# IHM.net
KiCad netlist of a schematic drawn in Altium Designer
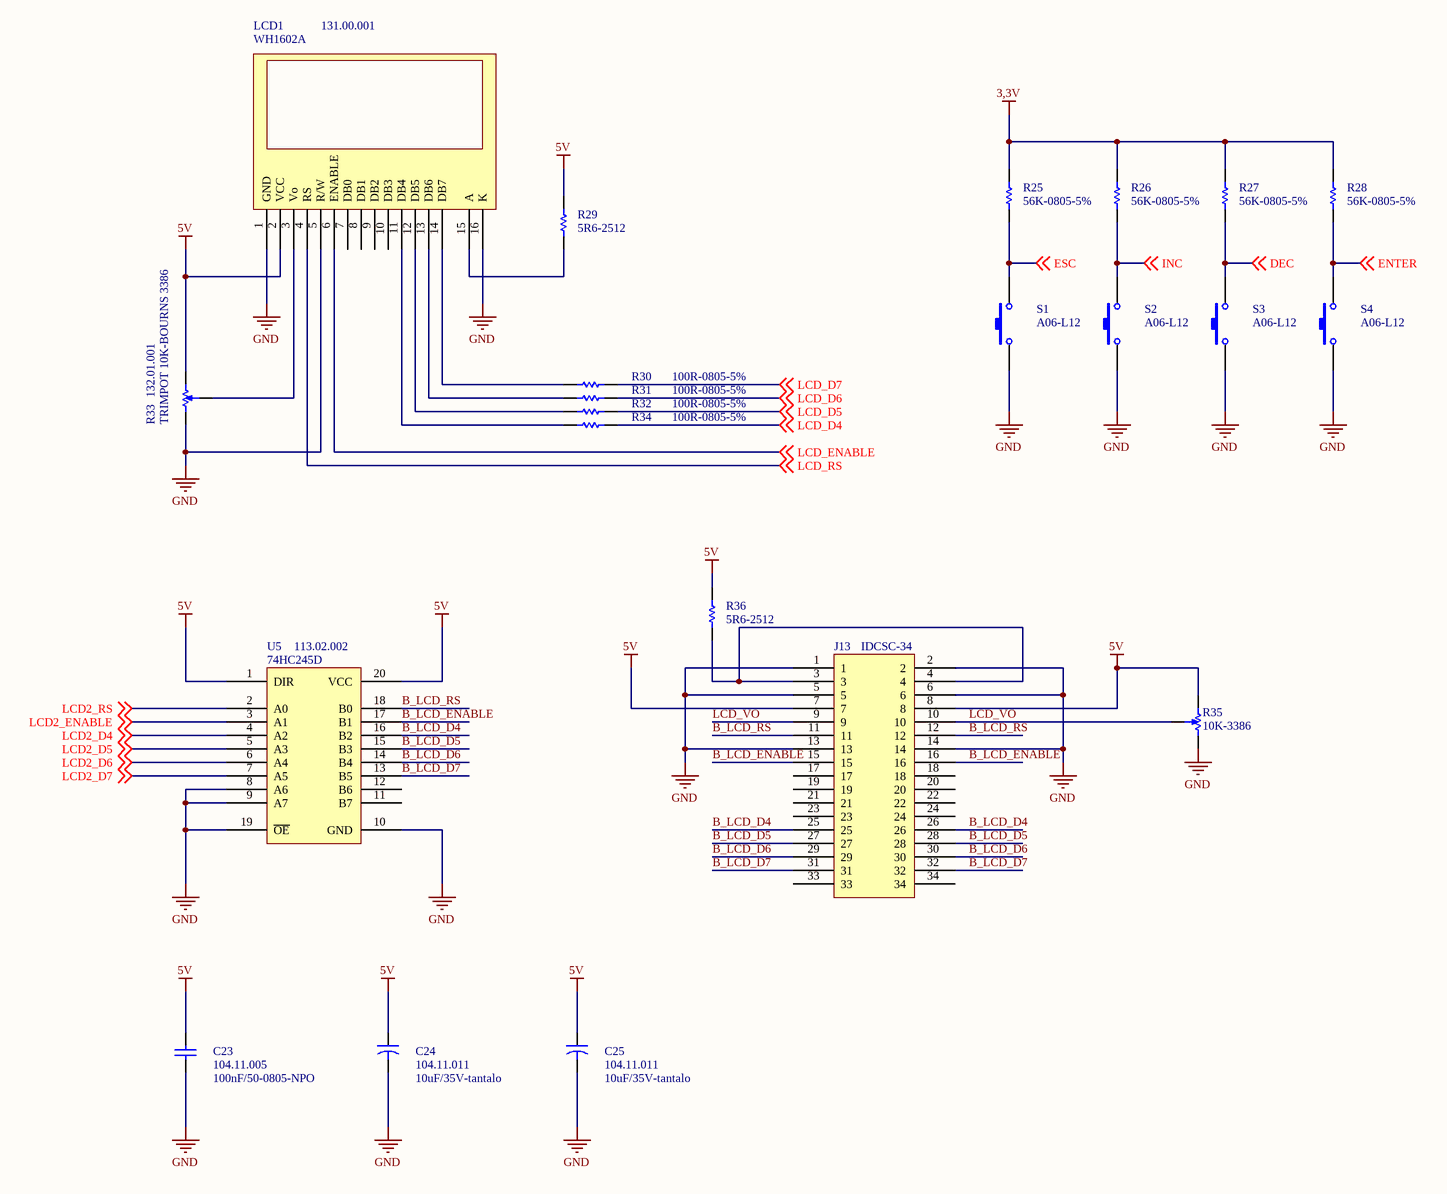
[diagram p0: IHM.SchDoc]

(export (version "E")
  (design (tool "Eeschema 10.0.6"))
  (components
    (comp (ref "C23")
      (value "100nF/50-0805-NPO")
      (footprint "0805-REVISADO ONDA")
      (fields (field (name "ERP") "104.11.005"))
      (libsource (lib "AquinoLib") (part "100nF/50-0805-NPO"))
    )
    (comp (ref "C24")
      (value "10uF/35V-tantalo")
      (footprint "CAP 2413 POLARIZADO KEMET")
      (fields (field (name "ERP") "104.11.011"))
      (libsource (lib "AquinoLib") (part "10uF/35V-tantalo"))
    )
    (comp (ref "C25")
      (value "10uF/35V-tantalo")
      (footprint "CAP 2413 POLARIZADO KEMET")
      (fields (field (name "ERP") "104.11.011"))
      (libsource (lib "AquinoLib") (part "10uF/35V-tantalo"))
    )
    (comp (ref "J13")
      (value "IDCSC-34")
      (footprint "IDCSC-34")
      (libsource (lib "AquinoLib") (part "IDCSC-34"))
    )
    (comp (ref "LCD1")
      (value "WH1602A")
      (footprint "WH1602")
      (fields (field (name "ERP") "131.00.001"))
      (libsource (lib "ChaveDigital3") (part "WH1602A"))
    )
    (comp (ref "R25")
      (value "56K-0805-5%")
      (footprint "0805-REVISADO ONDA")
      (libsource (lib "AquinoLib") (part "56K-0805-5%"))
    )
    (comp (ref "R26")
      (value "56K-0805-5%")
      (footprint "0805-REVISADO ONDA")
      (libsource (lib "AquinoLib") (part "56K-0805-5%"))
    )
    (comp (ref "R27")
      (value "56K-0805-5%")
      (footprint "0805-REVISADO ONDA")
      (libsource (lib "AquinoLib") (part "56K-0805-5%"))
    )
    (comp (ref "R28")
      (value "56K-0805-5%")
      (footprint "0805-REVISADO ONDA")
      (libsource (lib "AquinoLib") (part "56K-0805-5%"))
    )
    (comp (ref "R29")
      (value "5R6-2512")
      (footprint "2512 - REVISADO ONDA")
      (description "5R6-CR100")
      (libsource (lib "ChaveDigital3") (part "RES 5R6-CR100"))
    )
    (comp (ref "R30")
      (value "100R-0805-5%")
      (footprint "0805-revisado onda")
      (libsource (lib "AquinoLib") (part "100R-0805-5%"))
    )
    (comp (ref "R31")
      (value "100R-0805-5%")
      (footprint "0805-REVISADO ONDA")
      (libsource (lib "AquinoLib") (part "100R-0805-5%"))
    )
    (comp (ref "R32")
      (value "100R-0805-5%")
      (footprint "0805-REVISADO ONDA")
      (libsource (lib "AquinoLib") (part "100R-0805-5%"))
    )
    (comp (ref "R33")
      (value "TRIMPOT 10K-BOURNS 3386")
      (footprint "TRIMPOT 3386")
      (fields (field (name "ERP") "132.01.001"))
      (libsource (lib "ChaveDigital3") (part "TRIMPOT 3386 50K"))
    )
    (comp (ref "R34")
      (value "100R-0805-5%")
      (footprint "0805-REVISADO ONDA")
      (libsource (lib "AquinoLib") (part "100R-0805-5%"))
    )
    (comp (ref "R35")
      (value "10K-3386")
      (footprint "TRIMPOT 3386")
      (description "TRIMPOT 100K-0805-5%")
      (libsource (lib "AquinoLib") (part "TRIMPOT 10K-3386"))
    )
    (comp (ref "R36")
      (value "5R6-2512")
      (footprint "2512 - REVISADO ONDA")
      (description "5R6-CR100")
      (libsource (lib "ChaveDigital3") (part "RES 5R6-CR100"))
    )
    (comp (ref "S1")
      (value "A06-L12")
      (footprint "chave tactil nova")
      (libsource (lib "ChaveDigital3") (part "A06-L12"))
    )
    (comp (ref "S2")
      (value "A06-L12")
      (footprint "chave tactil nova")
      (libsource (lib "ChaveDigital3") (part "A06-L12"))
    )
    (comp (ref "S3")
      (value "A06-L12")
      (footprint "chave tactil nova")
      (libsource (lib "ChaveDigital3") (part "A06-L12"))
    )
    (comp (ref "S4")
      (value "A06-L12")
      (footprint "chave tactil nova")
      (libsource (lib "ChaveDigital3") (part "A06-L12"))
    )
    (comp (ref "U5")
      (value "74HC245D")
      (footprint "SOIC 20 FEITO A MÃO")
      (fields (field (name "ERP") "113.02.002"))
      (libsource (lib "ChaveDigital3") (part "74HC245D"))
    )
  )
  (nets
    (net (code "1") (name "/B_LCD_D4") (class "Default")
      (node (ref "J13") (pin "25") (pinfunction "25_25") (pintype "passive"))
      (node (ref "J13") (pin "26") (pinfunction "26_26") (pintype "passive"))
      (node (ref "U5") (pin "16") (pinfunction "B2_16") (pintype "passive"))
    )
    (net (code "2") (name "/B_LCD_D5") (class "Default")
      (node (ref "J13") (pin "27") (pinfunction "27_27") (pintype "passive"))
      (node (ref "J13") (pin "28") (pinfunction "28_28") (pintype "passive"))
      (node (ref "U5") (pin "15") (pinfunction "B3_15") (pintype "passive"))
    )
    (net (code "3") (name "/B_LCD_D6") (class "Default")
      (node (ref "J13") (pin "29") (pinfunction "29_29") (pintype "passive"))
      (node (ref "J13") (pin "30") (pinfunction "30_30") (pintype "passive"))
      (node (ref "U5") (pin "14") (pinfunction "B4_14") (pintype "passive"))
    )
    (net (code "4") (name "/B_LCD_D7") (class "Default")
      (node (ref "J13") (pin "31") (pinfunction "31_31") (pintype "passive"))
      (node (ref "J13") (pin "32") (pinfunction "32_32") (pintype "passive"))
      (node (ref "U5") (pin "13") (pinfunction "B5_13") (pintype "passive"))
    )
    (net (code "5") (name "/B_LCD_ENABLE") (class "Default")
      (node (ref "J13") (pin "15") (pinfunction "15_15") (pintype "passive"))
      (node (ref "J13") (pin "16") (pinfunction "16_16") (pintype "passive"))
      (node (ref "U5") (pin "17") (pinfunction "B1_17") (pintype "passive"))
    )
    (net (code "6") (name "/B_LCD_RS") (class "Default")
      (node (ref "J13") (pin "11") (pinfunction "11_11") (pintype "passive"))
      (node (ref "J13") (pin "12") (pinfunction "12_12") (pintype "passive"))
      (node (ref "U5") (pin "18") (pinfunction "B0_18") (pintype "passive"))
    )
    (net (code "7") (name "/LCD_VO") (class "Default")
      (node (ref "J13") (pin "10") (pinfunction "10_10") (pintype "passive"))
      (node (ref "J13") (pin "9") (pinfunction "9_9") (pintype "passive"))
      (node (ref "R35") (pin "2") (pinfunction "2_2") (pintype "passive"))
    )
    (net (code "8") (name "3,3V") (class "Default")
      (node (ref "R25") (pin "1") (pinfunction "1_1") (pintype "passive"))
      (node (ref "R26") (pin "1") (pinfunction "1_1") (pintype "passive"))
      (node (ref "R27") (pin "1") (pinfunction "1_1") (pintype "passive"))
      (node (ref "R28") (pin "1") (pinfunction "1_1") (pintype "passive"))
    )
    (net (code "9") (name "5V") (class "Default")
      (node (ref "C23") (pin "2") (pinfunction "2_2") (pintype "passive"))
      (node (ref "C24") (pin "1") (pinfunction "1_1") (pintype "passive"))
      (node (ref "C25") (pin "1") (pinfunction "1_1") (pintype "passive"))
      (node (ref "J13") (pin "7") (pinfunction "7_7") (pintype "passive"))
      (node (ref "J13") (pin "8") (pinfunction "8_8") (pintype "passive"))
      (node (ref "LCD1") (pin "2") (pinfunction "VCC_2") (pintype "passive"))
      (node (ref "R29") (pin "2") (pinfunction "2_2") (pintype "passive"))
      (node (ref "R33") (pin "1") (pinfunction "1_1") (pintype "passive"))
      (node (ref "R35") (pin "3") (pinfunction "3_3") (pintype "passive"))
      (node (ref "R36") (pin "2") (pinfunction "2_2") (pintype "passive"))
      (node (ref "U5") (pin "1") (pinfunction "DIR_1") (pintype "passive"))
      (node (ref "U5") (pin "20") (pinfunction "VCC_20") (pintype "passive"))
    )
    (net (code "10") (name "DEC") (class "Default")
      (node (ref "R27") (pin "2") (pinfunction "2_2") (pintype "passive"))
      (node (ref "S3") (pin "2") (pinfunction "2_2") (pintype "passive"))
    )
    (net (code "11") (name "ENTER") (class "Default")
      (node (ref "R28") (pin "2") (pinfunction "2_2") (pintype "passive"))
      (node (ref "S4") (pin "2") (pinfunction "2_2") (pintype "passive"))
    )
    (net (code "12") (name "ESC") (class "Default")
      (node (ref "R25") (pin "2") (pinfunction "2_2") (pintype "passive"))
      (node (ref "S1") (pin "2") (pinfunction "2_2") (pintype "passive"))
    )
    (net (code "13") (name "GND") (class "Default")
      (node (ref "C23") (pin "1") (pinfunction "1_1") (pintype "passive"))
      (node (ref "C24") (pin "2") (pinfunction "2_2") (pintype "passive"))
      (node (ref "C25") (pin "2") (pinfunction "2_2") (pintype "passive"))
      (node (ref "J13") (pin "1") (pinfunction "1_1") (pintype "passive"))
      (node (ref "J13") (pin "13") (pinfunction "13_13") (pintype "passive"))
      (node (ref "J13") (pin "14") (pinfunction "14_14") (pintype "passive"))
      (node (ref "J13") (pin "2") (pinfunction "2_2") (pintype "passive"))
      (node (ref "J13") (pin "5") (pinfunction "5_5") (pintype "passive"))
      (node (ref "J13") (pin "6") (pinfunction "6_6") (pintype "passive"))
      (node (ref "LCD1") (pin "1") (pinfunction "GND_1") (pintype "passive"))
      (node (ref "LCD1") (pin "16") (pinfunction "K_16") (pintype "passive"))
      (node (ref "LCD1") (pin "5") (pinfunction "R/W_5") (pintype "passive"))
      (node (ref "R33") (pin "3") (pinfunction "3_3") (pintype "passive"))
      (node (ref "R35") (pin "1") (pinfunction "1_1") (pintype "passive"))
      (node (ref "S1") (pin "1") (pinfunction "1_1") (pintype "passive"))
      (node (ref "S2") (pin "1") (pinfunction "1_1") (pintype "passive"))
      (node (ref "S3") (pin "1") (pinfunction "1_1") (pintype "passive"))
      (node (ref "S4") (pin "1") (pinfunction "1_1") (pintype "passive"))
      (node (ref "U5") (pin "10") (pinfunction "GND_10") (pintype "passive"))
      (node (ref "U5") (pin "19") (pinfunction "~{OE}_19") (pintype "passive"))
      (node (ref "U5") (pin "8") (pinfunction "A6_8") (pintype "passive"))
      (node (ref "U5") (pin "9") (pinfunction "A7_9") (pintype "passive"))
    )
    (net (code "14") (name "INC") (class "Default")
      (node (ref "R26") (pin "2") (pinfunction "2_2") (pintype "passive"))
      (node (ref "S2") (pin "2") (pinfunction "2_2") (pintype "passive"))
    )
    (net (code "15") (name "LCD2_D4") (class "Default")
      (node (ref "U5") (pin "4") (pinfunction "A2_4") (pintype "passive"))
    )
    (net (code "16") (name "LCD2_D5") (class "Default")
      (node (ref "U5") (pin "5") (pinfunction "A3_5") (pintype "passive"))
    )
    (net (code "17") (name "LCD2_D6") (class "Default")
      (node (ref "U5") (pin "6") (pinfunction "A4_6") (pintype "passive"))
    )
    (net (code "18") (name "LCD2_D7") (class "Default")
      (node (ref "U5") (pin "7") (pinfunction "A5_7") (pintype "passive"))
    )
    (net (code "19") (name "LCD2_ENABLE") (class "Default")
      (node (ref "U5") (pin "3") (pinfunction "A1_3") (pintype "passive"))
    )
    (net (code "20") (name "LCD2_RS") (class "Default")
      (node (ref "U5") (pin "2") (pinfunction "A0_2") (pintype "passive"))
    )
    (net (code "21") (name "LCD_D4") (class "Default")
      (node (ref "R34") (pin "2") (pinfunction "2_2") (pintype "passive"))
    )
    (net (code "22") (name "LCD_D5") (class "Default")
      (node (ref "R32") (pin "2") (pinfunction "2_2") (pintype "passive"))
    )
    (net (code "23") (name "LCD_D6") (class "Default")
      (node (ref "R31") (pin "2") (pinfunction "2_2") (pintype "passive"))
    )
    (net (code "24") (name "LCD_D7") (class "Default")
      (node (ref "R30") (pin "2") (pinfunction "2_2") (pintype "passive"))
    )
    (net (code "25") (name "LCD_ENABLE") (class "Default")
      (node (ref "LCD1") (pin "6") (pinfunction "ENABLE_6") (pintype "passive"))
    )
    (net (code "26") (name "LCD_RS") (class "Default")
      (node (ref "LCD1") (pin "4") (pinfunction "RS_4") (pintype "passive"))
    )
    (net (code "27") (name "Net-(J13-Pad3)") (class "Default")
      (node (ref "J13") (pin "3") (pinfunction "3_3") (pintype "passive"))
      (node (ref "J13") (pin "4") (pinfunction "4_4") (pintype "passive"))
      (node (ref "R36") (pin "1") (pinfunction "1_1") (pintype "passive"))
    )
    (net (code "28") (name "Net-(LCD1-A)") (class "Default")
      (node (ref "LCD1") (pin "15") (pinfunction "A_15") (pintype "passive"))
      (node (ref "R29") (pin "1") (pinfunction "1_1") (pintype "passive"))
    )
    (net (code "29") (name "Net-(LCD1-DB4)") (class "Default")
      (node (ref "LCD1") (pin "11") (pinfunction "DB4_11") (pintype "passive"))
      (node (ref "R34") (pin "1") (pinfunction "1_1") (pintype "passive"))
    )
    (net (code "30") (name "Net-(LCD1-DB5)") (class "Default")
      (node (ref "LCD1") (pin "12") (pinfunction "DB5_12") (pintype "passive"))
      (node (ref "R32") (pin "1") (pinfunction "1_1") (pintype "passive"))
    )
    (net (code "31") (name "Net-(LCD1-DB6)") (class "Default")
      (node (ref "LCD1") (pin "13") (pinfunction "DB6_13") (pintype "passive"))
      (node (ref "R31") (pin "1") (pinfunction "1_1") (pintype "passive"))
    )
    (net (code "32") (name "Net-(LCD1-DB7)") (class "Default")
      (node (ref "LCD1") (pin "14") (pinfunction "DB7_14") (pintype "passive"))
      (node (ref "R30") (pin "1") (pinfunction "1_1") (pintype "passive"))
    )
    (net (code "33") (name "Net-(LCD1-Vo)") (class "Default")
      (node (ref "LCD1") (pin "3") (pinfunction "Vo_3") (pintype "passive"))
      (node (ref "R33") (pin "2") (pinfunction "2_2") (pintype "passive"))
    )
    (net (code "34") (name "unconnected-(J13-Pad17)") (class "Default")
      (node (ref "J13") (pin "17") (pinfunction "17_17") (pintype "passive"))
    )
    (net (code "35") (name "unconnected-(J13-Pad18)") (class "Default")
      (node (ref "J13") (pin "18") (pinfunction "18_18") (pintype "passive"))
    )
    (net (code "36") (name "unconnected-(J13-Pad19)") (class "Default")
      (node (ref "J13") (pin "19") (pinfunction "19_19") (pintype "passive"))
    )
    (net (code "37") (name "unconnected-(J13-Pad20)") (class "Default")
      (node (ref "J13") (pin "20") (pinfunction "20_20") (pintype "passive"))
    )
    (net (code "38") (name "unconnected-(J13-Pad21)") (class "Default")
      (node (ref "J13") (pin "21") (pinfunction "21_21") (pintype "passive"))
    )
    (net (code "39") (name "unconnected-(J13-Pad22)") (class "Default")
      (node (ref "J13") (pin "22") (pinfunction "22_22") (pintype "passive"))
    )
    (net (code "40") (name "unconnected-(J13-Pad23)") (class "Default")
      (node (ref "J13") (pin "23") (pinfunction "23_23") (pintype "passive"))
    )
    (net (code "41") (name "unconnected-(J13-Pad24)") (class "Default")
      (node (ref "J13") (pin "24") (pinfunction "24_24") (pintype "passive"))
    )
    (net (code "42") (name "unconnected-(J13-Pad33)") (class "Default")
      (node (ref "J13") (pin "33") (pinfunction "33_33") (pintype "passive"))
    )
    (net (code "43") (name "unconnected-(J13-Pad34)") (class "Default")
      (node (ref "J13") (pin "34") (pinfunction "34_34") (pintype "passive"))
    )
    (net (code "44") (name "unconnected-(LCD1-DB0-Pad7)") (class "Default")
      (node (ref "LCD1") (pin "7") (pinfunction "DB0_7") (pintype "passive"))
    )
    (net (code "45") (name "unconnected-(LCD1-DB1-Pad8)") (class "Default")
      (node (ref "LCD1") (pin "8") (pinfunction "DB1_8") (pintype "passive"))
    )
    (net (code "46") (name "unconnected-(LCD1-DB2-Pad9)") (class "Default")
      (node (ref "LCD1") (pin "9") (pinfunction "DB2_9") (pintype "passive"))
    )
    (net (code "47") (name "unconnected-(LCD1-DB3-Pad10)") (class "Default")
      (node (ref "LCD1") (pin "10") (pinfunction "DB3_10") (pintype "passive"))
    )
    (net (code "48") (name "unconnected-(U5-B6-Pad12)") (class "Default")
      (node (ref "U5") (pin "12") (pinfunction "B6_12") (pintype "passive"))
    )
    (net (code "49") (name "unconnected-(U5-B7-Pad11)") (class "Default")
      (node (ref "U5") (pin "11") (pinfunction "B7_11") (pintype "passive"))
    )
  )
)
